# motor_driver_digital.net
KiCad netlist of a schematic drawn in EAGLE
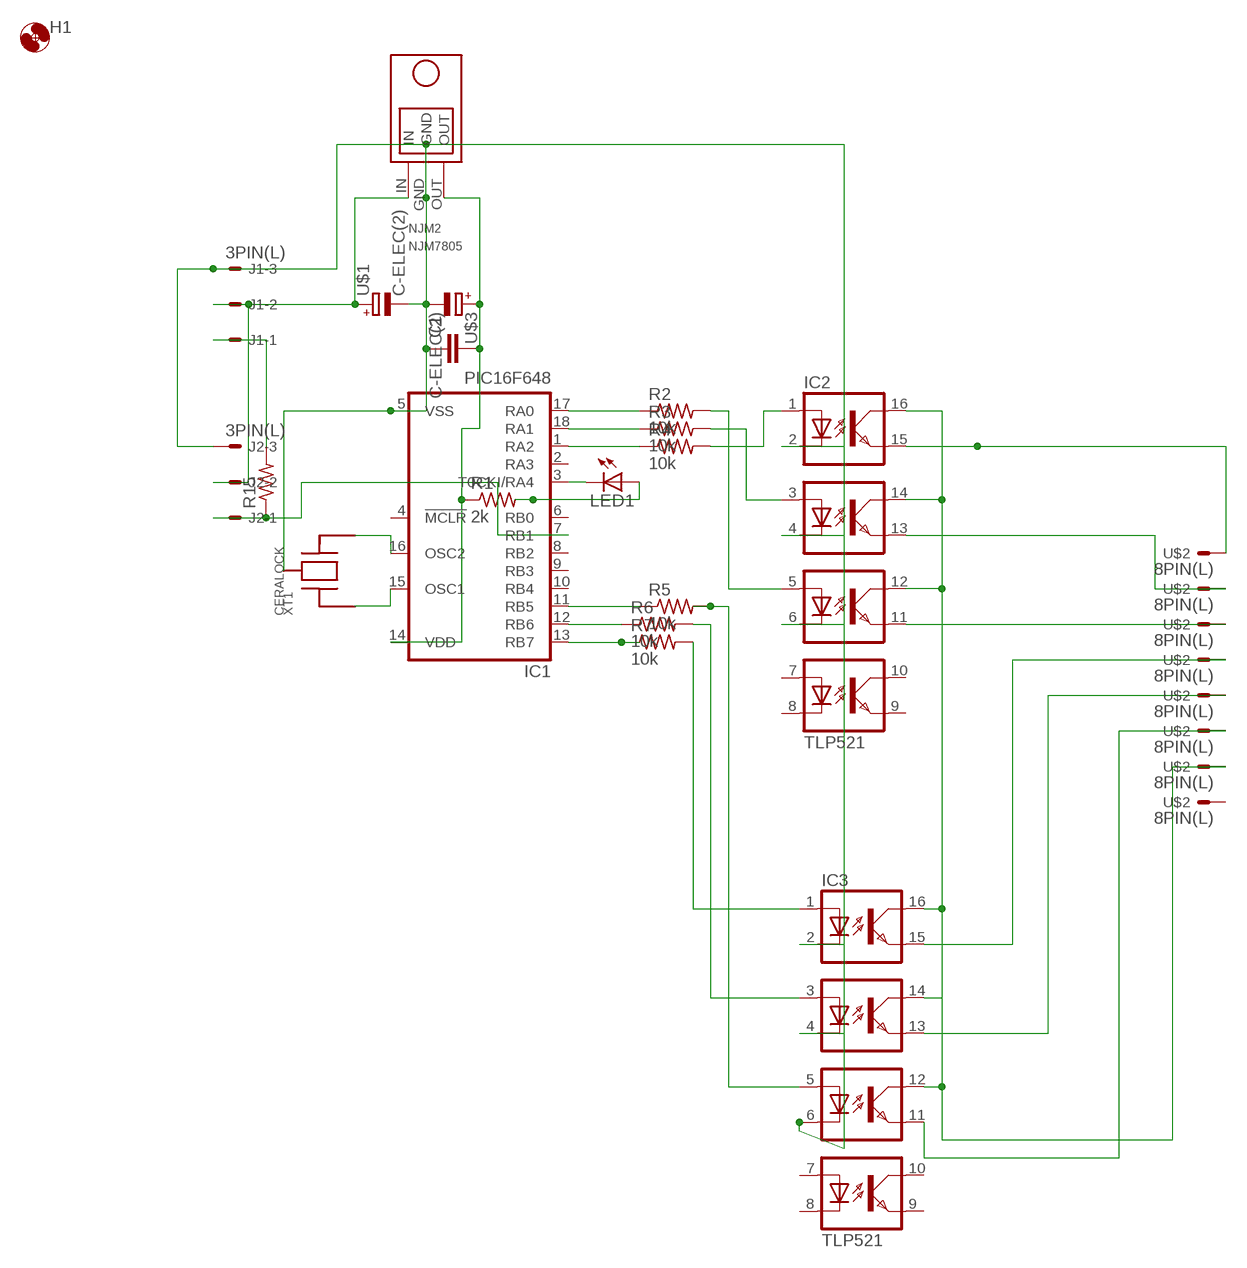
[diagram p0: schematic, sheet 1]

(export (version "E")
  (design (tool "Eeschema 10.0.6"))
  (components
    (comp (ref "C1")
      (value "C-")
      (footprint "eagle-import:C-2.54")
      (libsource (lib "eagle-import") (part "C-"))
    )
    (comp (ref "H1")
      (value "HOLE3.3M3BOLT")
      (footprint "eagle-import:HOLE3.3")
      (libsource (lib "eagle-import") (part "HOLE3.3M3BOLT"))
    )
    (comp (ref "IC1")
      (value "PIC16F648")
      (footprint "eagle-import:DIL18")
      (libsource (lib "eagle-import") (part "PIC16F648"))
    )
    (comp (ref "IC2")
      (value "TLP521")
      (footprint "eagle-import:DIL16")
      (libsource (lib "eagle-import") (part "TLP521"))
    )
    (comp (ref "IC3")
      (value "TLP521")
      (footprint "eagle-import:DIL16")
      (libsource (lib "eagle-import") (part "TLP521"))
    )
    (comp (ref "J1")
      (value "3PIN(L)")
      (footprint "eagle-import:3PL")
      (libsource (lib "eagle-import") (part "3PIN(L)"))
    )
    (comp (ref "J2")
      (value "3PIN(L)")
      (footprint "eagle-import:3PL")
      (libsource (lib "eagle-import") (part "3PIN(L)"))
    )
    (comp (ref "LED1")
      (value "LED")
      (footprint "eagle-import:LED5MM")
      (libsource (lib "eagle-import") (part "LED"))
    )
    (comp (ref "NJM2")
      (value "NJM7805")
      (footprint "eagle-import:NJM7805")
      (libsource (lib "eagle-import") (part "NJM7805"))
    )
    (comp (ref "R1")
      (value "2k")
      (footprint "eagle-import:0207_10")
      (libsource (lib "eagle-import") (part "R-"))
    )
    (comp (ref "R2")
      (value "10k")
      (footprint "eagle-import:0207_10")
      (libsource (lib "eagle-import") (part "R-"))
    )
    (comp (ref "R3")
      (value "10k")
      (footprint "eagle-import:0207_10")
      (libsource (lib "eagle-import") (part "R-"))
    )
    (comp (ref "R4")
      (value "10k")
      (footprint "eagle-import:0207_10")
      (libsource (lib "eagle-import") (part "R-"))
    )
    (comp (ref "R5")
      (value "10k")
      (footprint "eagle-import:0207_10")
      (libsource (lib "eagle-import") (part "R-"))
    )
    (comp (ref "R6")
      (value "10k")
      (footprint "eagle-import:0207_10")
      (libsource (lib "eagle-import") (part "R-"))
    )
    (comp (ref "R7")
      (value "10k")
      (footprint "eagle-import:0207_10")
      (libsource (lib "eagle-import") (part "R-"))
    )
    (comp (ref "R15")
      (value "R-")
      (footprint "eagle-import:0207_10")
      (libsource (lib "eagle-import") (part "R-"))
    )
    (comp (ref "U$1")
      (value "C-ELEC(2)")
      (footprint "eagle-import:C-6MM(2)")
      (libsource (lib "eagle-import") (part "C-ELEC(2)"))
    )
    (comp (ref "U$2")
      (value "8PIN(L)")
      (footprint "eagle-import:8PL")
      (libsource (lib "eagle-import") (part "8PIN(L)"))
    )
    (comp (ref "U$3")
      (value "C-ELEC(2)")
      (footprint "eagle-import:C-6MM(2)")
      (libsource (lib "eagle-import") (part "C-ELEC(2)"))
    )
    (comp (ref "XT1")
      (value "CERALOCK")
      (footprint "eagle-import:CERALOCK")
      (libsource (lib "eagle-import") (part "CERALOCK"))
    )
  )
  (nets
    (net (code "1") (name "Net-(C1-1)") (class "Default")
      (node (ref "C1") (pin "P$1") (pinfunction "1_P$1") (pintype "passive"))
      (node (ref "IC1") (pin "5") (pinfunction "VSS_5") (pintype "power_in"))
      (node (ref "IC2") (pin "2") (pinfunction "C0_2") (pintype "passive"))
      (node (ref "IC2") (pin "4") (pinfunction "C1_4") (pintype "passive"))
      (node (ref "IC2") (pin "6") (pinfunction "C2_6") (pintype "passive"))
      (node (ref "IC3") (pin "2") (pinfunction "C0_2") (pintype "passive"))
      (node (ref "IC3") (pin "4") (pinfunction "C1_4") (pintype "passive"))
      (node (ref "IC3") (pin "6") (pinfunction "C2_6") (pintype "passive"))
      (node (ref "J1") (pin "3") (pinfunction "S_3") (pintype "passive"))
      (node (ref "J2") (pin "3") (pinfunction "S_3") (pintype "passive"))
      (node (ref "NJM2") (pin "GND") (pinfunction "GND_GND") (pintype "bidirectional"))
      (node (ref "U$1") (pin "-") (pinfunction "-_-") (pintype "passive"))
      (node (ref "U$3") (pin "-") (pinfunction "-_-") (pintype "passive"))
      (node (ref "XT1") (pin "P2") (pinfunction "2_P2") (pintype "passive"))
    )
    (net (code "2") (name "Net-(C1-2)") (class "Default")
      (node (ref "C1") (pin "P$2") (pinfunction "2_P$2") (pintype "passive"))
      (node (ref "IC1") (pin "14") (pinfunction "VDD_14") (pintype "power_in"))
      (node (ref "NJM2") (pin "OUT") (pinfunction "OUT_OUT") (pintype "bidirectional"))
      (node (ref "R1") (pin "1") (pinfunction "1_1") (pintype "passive"))
      (node (ref "U$3") (pin "+") (pinfunction "+_+") (pintype "passive"))
    )
    (net (code "3") (name "Net-(IC1-OSC1)") (class "Default")
      (node (ref "IC1") (pin "15") (pinfunction "OSC1_15") (pintype "input"))
      (node (ref "XT1") (pin "P1") (pinfunction "1_P1") (pintype "passive"))
    )
    (net (code "4") (name "Net-(IC1-OSC2)") (class "Default")
      (node (ref "IC1") (pin "16") (pinfunction "OSC2_16") (pintype "output"))
      (node (ref "XT1") (pin "P3") (pinfunction "3_P3") (pintype "passive"))
    )
    (net (code "5") (name "Net-(IC1-RA0)") (class "Default")
      (node (ref "IC1") (pin "17") (pinfunction "RA0_17") (pintype "bidirectional"))
      (node (ref "R2") (pin "1") (pinfunction "1_1") (pintype "passive"))
    )
    (net (code "6") (name "Net-(IC1-RA1)") (class "Default")
      (node (ref "IC1") (pin "18") (pinfunction "RA1_18") (pintype "bidirectional"))
      (node (ref "R3") (pin "1") (pinfunction "1_1") (pintype "passive"))
    )
    (net (code "7") (name "Net-(IC1-RA2)") (class "Default")
      (node (ref "IC1") (pin "1") (pinfunction "RA2_1") (pintype "bidirectional"))
      (node (ref "R4") (pin "1") (pinfunction "1_1") (pintype "passive"))
    )
    (net (code "8") (name "Net-(IC1-RB1)") (class "Default")
      (node (ref "IC1") (pin "7") (pinfunction "RB1_7") (pintype "bidirectional"))
      (node (ref "J2") (pin "1") (pinfunction "S_1") (pintype "passive"))
      (node (ref "R15") (pin "1") (pinfunction "1_1") (pintype "passive"))
    )
    (net (code "9") (name "Net-(IC1-RB5)") (class "Default")
      (node (ref "IC1") (pin "11") (pinfunction "RB5_11") (pintype "bidirectional"))
      (node (ref "R5") (pin "1") (pinfunction "1_1") (pintype "passive"))
    )
    (net (code "10") (name "Net-(IC1-RB6)") (class "Default")
      (node (ref "IC1") (pin "12") (pinfunction "RB6_12") (pintype "bidirectional"))
      (node (ref "R6") (pin "1") (pinfunction "1_1") (pintype "passive"))
    )
    (net (code "11") (name "Net-(IC1-RB7)") (class "Default")
      (node (ref "IC1") (pin "13") (pinfunction "RB7_13") (pintype "bidirectional"))
      (node (ref "R7") (pin "1") (pinfunction "1_1") (pintype "passive"))
    )
    (net (code "12") (name "Net-(IC1-T0CKI{slash}RA4)") (class "Default")
      (node (ref "IC1") (pin "3") (pinfunction "T0CKI/RA4_3") (pintype "bidirectional"))
      (node (ref "LED1") (pin "K") (pinfunction "C_K") (pintype "passive"))
    )
    (net (code "13") (name "Net-(IC2-A0)") (class "Default")
      (node (ref "IC2") (pin "1") (pinfunction "A0_1") (pintype "passive"))
      (node (ref "R4") (pin "2") (pinfunction "2_2") (pintype "passive"))
    )
    (net (code "14") (name "Net-(IC2-A1)") (class "Default")
      (node (ref "IC2") (pin "3") (pinfunction "A1_3") (pintype "passive"))
      (node (ref "R3") (pin "2") (pinfunction "2_2") (pintype "passive"))
    )
    (net (code "15") (name "Net-(IC2-A2)") (class "Default")
      (node (ref "IC2") (pin "5") (pinfunction "A2_5") (pintype "passive"))
      (node (ref "R2") (pin "2") (pinfunction "2_2") (pintype "passive"))
    )
    (net (code "16") (name "Net-(IC2-COL0)") (class "Default")
      (node (ref "IC2") (pin "12") (pinfunction "COL2_12") (pintype "passive"))
      (node (ref "IC2") (pin "14") (pinfunction "COL1_14") (pintype "passive"))
      (node (ref "IC2") (pin "16") (pinfunction "COL0_16") (pintype "passive"))
      (node (ref "IC3") (pin "12") (pinfunction "COL2_12") (pintype "passive"))
      (node (ref "IC3") (pin "14") (pinfunction "COL1_14") (pintype "passive"))
      (node (ref "IC3") (pin "16") (pinfunction "COL0_16") (pintype "passive"))
      (node (ref "U$2") (pin "P7") (pinfunction "P7_P7") (pintype "passive"))
    )
    (net (code "17") (name "Net-(IC2-EMIT0)") (class "Default")
      (node (ref "IC2") (pin "15") (pinfunction "EMIT0_15") (pintype "passive"))
      (node (ref "U$2") (pin "P1") (pinfunction "P1_P1") (pintype "passive"))
    )
    (net (code "18") (name "Net-(IC2-EMIT1)") (class "Default")
      (node (ref "IC2") (pin "13") (pinfunction "EMIT1_13") (pintype "passive"))
      (node (ref "U$2") (pin "P2") (pinfunction "P2_P2") (pintype "passive"))
    )
    (net (code "19") (name "Net-(IC2-EMIT2)") (class "Default")
      (node (ref "IC2") (pin "11") (pinfunction "EMIT2_11") (pintype "passive"))
      (node (ref "U$2") (pin "P3") (pinfunction "P3_P3") (pintype "passive"))
    )
    (net (code "20") (name "Net-(IC3-A0)") (class "Default")
      (node (ref "IC3") (pin "1") (pinfunction "A0_1") (pintype "passive"))
      (node (ref "R7") (pin "2") (pinfunction "2_2") (pintype "passive"))
    )
    (net (code "21") (name "Net-(IC3-A1)") (class "Default")
      (node (ref "IC3") (pin "3") (pinfunction "A1_3") (pintype "passive"))
      (node (ref "R6") (pin "2") (pinfunction "2_2") (pintype "passive"))
    )
    (net (code "22") (name "Net-(IC3-A2)") (class "Default")
      (node (ref "IC3") (pin "5") (pinfunction "A2_5") (pintype "passive"))
      (node (ref "R5") (pin "2") (pinfunction "2_2") (pintype "passive"))
    )
    (net (code "23") (name "Net-(IC3-EMIT0)") (class "Default")
      (node (ref "IC3") (pin "15") (pinfunction "EMIT0_15") (pintype "passive"))
      (node (ref "U$2") (pin "P4") (pinfunction "P4_P4") (pintype "passive"))
    )
    (net (code "24") (name "Net-(IC3-EMIT1)") (class "Default")
      (node (ref "IC3") (pin "13") (pinfunction "EMIT1_13") (pintype "passive"))
      (node (ref "U$2") (pin "P5") (pinfunction "P5_P5") (pintype "passive"))
    )
    (net (code "25") (name "Net-(IC3-EMIT2)") (class "Default")
      (node (ref "IC3") (pin "11") (pinfunction "EMIT2_11") (pintype "passive"))
      (node (ref "U$2") (pin "P6") (pinfunction "P6_P6") (pintype "passive"))
    )
    (net (code "26") (name "Net-(J1A-S)") (class "Default")
      (node (ref "J1") (pin "1") (pinfunction "S_1") (pintype "passive"))
      (node (ref "R15") (pin "2") (pinfunction "2_2") (pintype "passive"))
    )
    (net (code "27") (name "Net-(J1B-S)") (class "Default")
      (node (ref "J1") (pin "2") (pinfunction "S_2") (pintype "passive"))
      (node (ref "J2") (pin "2") (pinfunction "S_2") (pintype "passive"))
      (node (ref "NJM2") (pin "IN") (pinfunction "IN_IN") (pintype "bidirectional"))
      (node (ref "U$1") (pin "+") (pinfunction "+_+") (pintype "passive"))
    )
    (net (code "28") (name "Net-(LED1-PadA)") (class "Default")
      (node (ref "LED1") (pin "A") (pinfunction "A_A") (pintype "passive"))
      (node (ref "R1") (pin "2") (pinfunction "2_2") (pintype "passive"))
    )
    (net (code "29") (name "unconnected-(IC1-RA3-Pad2)") (class "Default")
      (node (ref "IC1") (pin "2") (pinfunction "RA3_2") (pintype "bidirectional"))
    )
    (net (code "30") (name "unconnected-(IC1-RB0-Pad6)") (class "Default")
      (node (ref "IC1") (pin "6") (pinfunction "RB0_6") (pintype "bidirectional"))
    )
    (net (code "31") (name "unconnected-(IC1-RB2-Pad8)") (class "Default")
      (node (ref "IC1") (pin "8") (pinfunction "RB2_8") (pintype "bidirectional"))
    )
    (net (code "32") (name "unconnected-(IC1-RB3-Pad9)") (class "Default")
      (node (ref "IC1") (pin "9") (pinfunction "RB3_9") (pintype "bidirectional"))
    )
    (net (code "33") (name "unconnected-(IC1-RB4-Pad10)") (class "Default")
      (node (ref "IC1") (pin "10") (pinfunction "RB4_10") (pintype "bidirectional"))
    )
    (net (code "34") (name "unconnected-(IC1-~{MCLR}-Pad4)") (class "Default")
      (node (ref "IC1") (pin "4") (pinfunction "~{MCLR}_4") (pintype "input"))
    )
    (net (code "35") (name "unconnected-(IC2-A3-Pad7)") (class "Default")
      (node (ref "IC2") (pin "7") (pinfunction "A3_7") (pintype "passive"))
    )
    (net (code "36") (name "unconnected-(IC2-C3-Pad8)") (class "Default")
      (node (ref "IC2") (pin "8") (pinfunction "C3_8") (pintype "passive"))
    )
    (net (code "37") (name "unconnected-(IC2-COL3-Pad10)") (class "Default")
      (node (ref "IC2") (pin "10") (pinfunction "COL3_10") (pintype "passive"))
    )
    (net (code "38") (name "unconnected-(IC2-EMIT3-Pad9)") (class "Default")
      (node (ref "IC2") (pin "9") (pinfunction "EMIT3_9") (pintype "passive"))
    )
    (net (code "39") (name "unconnected-(IC3-A3-Pad7)") (class "Default")
      (node (ref "IC3") (pin "7") (pinfunction "A3_7") (pintype "passive"))
    )
    (net (code "40") (name "unconnected-(IC3-C3-Pad8)") (class "Default")
      (node (ref "IC3") (pin "8") (pinfunction "C3_8") (pintype "passive"))
    )
    (net (code "41") (name "unconnected-(IC3-COL3-Pad10)") (class "Default")
      (node (ref "IC3") (pin "10") (pinfunction "COL3_10") (pintype "passive"))
    )
    (net (code "42") (name "unconnected-(IC3-EMIT3-Pad9)") (class "Default")
      (node (ref "IC3") (pin "9") (pinfunction "EMIT3_9") (pintype "passive"))
    )
    (net (code "43") (name "unconnected-(U$2-PadP8)") (class "Default")
      (node (ref "U$2") (pin "P8") (pinfunction "P8_P8") (pintype "passive"))
    )
  )
)
